# lato1.net
KiCad netlist of a schematic drawn in EAGLE
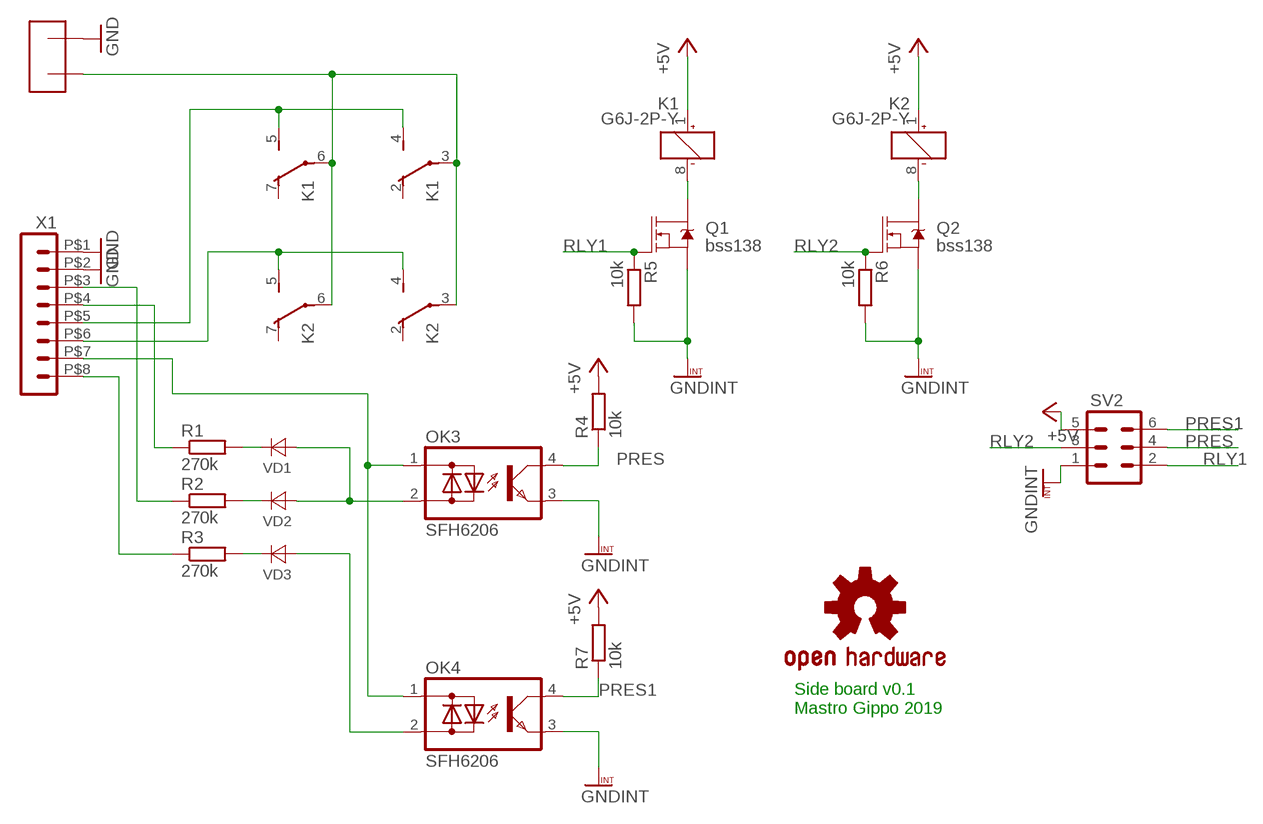
[diagram p0: schematic, sheet 1]

(export (version "E")
  (design (tool "Eeschema 10.0.6"))
  (components
    (comp (ref "K1")
      (value "G6J-2P-Y")
      (footprint "eagle-import:G6J-2P-Y")
      (fields (field (name "MF") "OMRON COMPONENTS USA") (field (name "MPN") "G6J-2P-Y-DC12"))
      (libsource (lib "eagle-import") (part "G6J-2?-YP"))
    )
    (comp (ref "K2")
      (value "G6J-2P-Y")
      (footprint "eagle-import:G6J-2P-Y")
      (fields (field (name "MF") "OMRON COMPONENTS USA") (field (name "MPN") "G6J-2P-Y-DC12"))
      (libsource (lib "eagle-import") (part "G6J-2?-YP"))
    )
    (comp (ref "OK3")
      (value "SFH6206")
      (footprint "eagle-import:DIL4-SMD")
      (fields (field (name "MF") "VISHAY/TELEFUNKEN") (field (name "MPN") "SFH6206-3"))
      (libsource (lib "eagle-import") (part "SFH6206"))
    )
    (comp (ref "OK4")
      (value "SFH6206")
      (footprint "eagle-import:DIL4-SMD")
      (fields (field (name "MF") "VISHAY/TELEFUNKEN") (field (name "MPN") "SFH6206-3"))
      (libsource (lib "eagle-import") (part "SFH6206"))
    )
    (comp (ref "Q1")
      (value "bss138")
      (footprint "eagle-import:SOT23-3")
      (libsource (lib "eagle-import") (part "MOSFET-NCH-BSS138"))
    )
    (comp (ref "Q2")
      (value "bss138")
      (footprint "eagle-import:SOT23-3")
      (libsource (lib "eagle-import") (part "MOSFET-NCH-BSS138"))
    )
    (comp (ref "R1")
      (value "270k")
      (footprint "eagle-import:R1210")
      (libsource (lib "eagle-import") (part "R-EU_R1210"))
    )
    (comp (ref "R2")
      (value "270k")
      (footprint "eagle-import:R1210")
      (libsource (lib "eagle-import") (part "R-EU_R1210"))
    )
    (comp (ref "R3")
      (value "270k")
      (footprint "eagle-import:R1210")
      (libsource (lib "eagle-import") (part "R-EU_R1210"))
    )
    (comp (ref "R4")
      (value "10k")
      (footprint "eagle-import:R0805")
      (libsource (lib "eagle-import") (part "R-EU_R0805"))
    )
    (comp (ref "R5")
      (value "10k")
      (footprint "eagle-import:R0805")
      (libsource (lib "eagle-import") (part "R-EU_R0805"))
    )
    (comp (ref "R6")
      (value "10k")
      (footprint "eagle-import:R0805")
      (libsource (lib "eagle-import") (part "R-EU_R0805"))
    )
    (comp (ref "R7")
      (value "10k")
      (footprint "eagle-import:R0805")
      (libsource (lib "eagle-import") (part "R-EU_R0805"))
    )
    (comp (ref "SV2")
      (value "MA03-2")
      (footprint "eagle-import:MA03-2")
      (libsource (lib "eagle-import") (part "MA03-2"))
    )
    (comp (ref "U$1")
      (value "ISOLATED_2P")
      (footprint "eagle-import:STRIP_NOMIDDLE")
      (libsource (lib "eagle-import") (part "ISOLATED_2P"))
    )
    (comp (ref "U$2")
      (value "OSHW-LOGOS")
      (footprint "eagle-import:OSHW-LOGO-S")
      (libsource (lib "eagle-import") (part "OSHW-LOGOS"))
    )
    (comp (ref "VD1")
      (value "DIODE-STANDARD-SOD323")
      (footprint "eagle-import:SOD323")
      (libsource (lib "eagle-import") (part "DIODE-STANDARD-SOD323"))
    )
    (comp (ref "VD2")
      (value "DIODE-STANDARD-SOD323")
      (footprint "eagle-import:SOD323")
      (libsource (lib "eagle-import") (part "DIODE-STANDARD-SOD323"))
    )
    (comp (ref "VD3")
      (value "DIODE-STANDARD-SOD323")
      (footprint "eagle-import:SOD323")
      (libsource (lib "eagle-import") (part "DIODE-STANDARD-SOD323"))
    )
    (comp (ref "X1")
      (value "HEADER_POS8_43045-0812")
      (footprint "eagle-import:43045-0812")
      (libsource (lib "eagle-import") (part "HEADER_POS8_?43045-0812"))
    )
  )
  (nets
    (net (code "1") (name "+5V") (class "Default")
      (node (ref "K1") (pin "1") (pinfunction "+_1") (pintype "passive"))
      (node (ref "K2") (pin "1") (pinfunction "+_1") (pintype "passive"))
      (node (ref "R4") (pin "2") (pinfunction "2_2") (pintype "passive"))
      (node (ref "R7") (pin "2") (pinfunction "2_2") (pintype "passive"))
      (node (ref "SV2") (pin "5") (pinfunction "5_5") (pintype "passive"))
    )
    (net (code "2") (name "/PRES") (class "Default")
      (node (ref "OK3") (pin "4") (pinfunction "C_4") (pintype "passive"))
      (node (ref "R4") (pin "1") (pinfunction "1_1") (pintype "passive"))
      (node (ref "SV2") (pin "4") (pinfunction "4_4") (pintype "passive"))
    )
    (net (code "3") (name "/PRES1") (class "Default")
      (node (ref "OK4") (pin "4") (pinfunction "C_4") (pintype "passive"))
      (node (ref "R7") (pin "1") (pinfunction "1_1") (pintype "passive"))
      (node (ref "SV2") (pin "6") (pinfunction "6_6") (pintype "passive"))
    )
    (net (code "4") (name "/RLY1") (class "Default")
      (node (ref "Q1") (pin "1") (pinfunction "G_1") (pintype "bidirectional"))
      (node (ref "R5") (pin "1") (pinfunction "1_1") (pintype "passive"))
      (node (ref "SV2") (pin "2") (pinfunction "2_2") (pintype "passive"))
    )
    (net (code "5") (name "/RLY2") (class "Default")
      (node (ref "Q2") (pin "1") (pinfunction "G_1") (pintype "bidirectional"))
      (node (ref "R6") (pin "1") (pinfunction "1_1") (pintype "passive"))
      (node (ref "SV2") (pin "3") (pinfunction "3_3") (pintype "passive"))
    )
    (net (code "6") (name "GND") (class "Default")
      (node (ref "U$1") (pin "P$1") (pinfunction "P$1_P$1") (pintype "bidirectional"))
      (node (ref "X1") (pin "P$1") (pinfunction "1_P$1") (pintype "passive"))
      (node (ref "X1") (pin "P$2") (pinfunction "2_P$2") (pintype "passive"))
    )
    (net (code "7") (name "GNDINT") (class "Default")
      (node (ref "OK3") (pin "3") (pinfunction "E_3") (pintype "passive"))
      (node (ref "OK4") (pin "3") (pinfunction "E_3") (pintype "passive"))
      (node (ref "Q1") (pin "2") (pinfunction "S_2") (pintype "bidirectional"))
      (node (ref "Q2") (pin "2") (pinfunction "S_2") (pintype "bidirectional"))
      (node (ref "R5") (pin "2") (pinfunction "2_2") (pintype "passive"))
      (node (ref "R6") (pin "2") (pinfunction "2_2") (pintype "passive"))
      (node (ref "SV2") (pin "1") (pinfunction "1_1") (pintype "passive"))
    )
    (net (code "8") (name "Net-(K1A--)") (class "Default")
      (node (ref "K1") (pin "8") (pinfunction "-_8") (pintype "passive"))
      (node (ref "Q1") (pin "3") (pinfunction "D_3") (pintype "bidirectional"))
    )
    (net (code "9") (name "Net-(K1B-P)") (class "Default")
      (node (ref "K1") (pin "3") (pinfunction "P_3") (pintype "passive"))
      (node (ref "K1") (pin "6") (pinfunction "P_6") (pintype "passive"))
      (node (ref "K2") (pin "3") (pinfunction "P_3") (pintype "passive"))
      (node (ref "K2") (pin "6") (pinfunction "P_6") (pintype "passive"))
      (node (ref "U$1") (pin "P$2") (pinfunction "P$2_P$2") (pintype "bidirectional"))
    )
    (net (code "10") (name "Net-(K1B-S)") (class "Default")
      (node (ref "K1") (pin "4") (pinfunction "S_4") (pintype "passive"))
      (node (ref "K1") (pin "5") (pinfunction "S_5") (pintype "passive"))
      (node (ref "X1") (pin "P$5") (pinfunction "5_P$5") (pintype "passive"))
    )
    (net (code "11") (name "Net-(K2A--)") (class "Default")
      (node (ref "K2") (pin "8") (pinfunction "-_8") (pintype "passive"))
      (node (ref "Q2") (pin "3") (pinfunction "D_3") (pintype "bidirectional"))
    )
    (net (code "12") (name "Net-(K2B-S)") (class "Default")
      (node (ref "K2") (pin "4") (pinfunction "S_4") (pintype "passive"))
      (node (ref "K2") (pin "5") (pinfunction "S_5") (pintype "passive"))
      (node (ref "X1") (pin "P$6") (pinfunction "6_P$6") (pintype "passive"))
    )
    (net (code "13") (name "Net-(OK3-AC1)") (class "Default")
      (node (ref "OK3") (pin "1") (pinfunction "AC1_1") (pintype "passive"))
      (node (ref "OK4") (pin "1") (pinfunction "AC1_1") (pintype "passive"))
      (node (ref "X1") (pin "P$7") (pinfunction "7_P$7") (pintype "passive"))
    )
    (net (code "14") (name "Net-(OK3-AC2)") (class "Default")
      (node (ref "OK3") (pin "2") (pinfunction "AC2_2") (pintype "passive"))
      (node (ref "VD1") (pin "A") (pinfunction "A_A") (pintype "passive"))
      (node (ref "VD2") (pin "A") (pinfunction "A_A") (pintype "passive"))
    )
    (net (code "15") (name "Net-(OK4-AC2)") (class "Default")
      (node (ref "OK4") (pin "2") (pinfunction "AC2_2") (pintype "passive"))
      (node (ref "VD3") (pin "A") (pinfunction "A_A") (pintype "passive"))
    )
    (net (code "16") (name "Net-(R1-Pad2)") (class "Default")
      (node (ref "R1") (pin "2") (pinfunction "2_2") (pintype "passive"))
      (node (ref "VD1") (pin "C") (pinfunction "C_C") (pintype "passive"))
    )
    (net (code "17") (name "Net-(R2-Pad2)") (class "Default")
      (node (ref "R2") (pin "2") (pinfunction "2_2") (pintype "passive"))
      (node (ref "VD2") (pin "C") (pinfunction "C_C") (pintype "passive"))
    )
    (net (code "18") (name "Net-(R3-Pad2)") (class "Default")
      (node (ref "R3") (pin "2") (pinfunction "2_2") (pintype "passive"))
      (node (ref "VD3") (pin "C") (pinfunction "C_C") (pintype "passive"))
    )
    (net (code "19") (name "Net-(X1-3)") (class "Default")
      (node (ref "R2") (pin "1") (pinfunction "1_1") (pintype "passive"))
      (node (ref "X1") (pin "P$3") (pinfunction "3_P$3") (pintype "passive"))
    )
    (net (code "20") (name "Net-(X1-4)") (class "Default")
      (node (ref "R1") (pin "1") (pinfunction "1_1") (pintype "passive"))
      (node (ref "X1") (pin "P$4") (pinfunction "4_P$4") (pintype "passive"))
    )
    (net (code "21") (name "Net-(X1-8)") (class "Default")
      (node (ref "R3") (pin "1") (pinfunction "1_1") (pintype "passive"))
      (node (ref "X1") (pin "P$8") (pinfunction "8_P$8") (pintype "passive"))
    )
    (net (code "22") (name "unconnected-(K1B-O-Pad2)") (class "Default")
      (node (ref "K1") (pin "2") (pinfunction "O_2") (pintype "passive"))
    )
    (net (code "23") (name "unconnected-(K1C-O-Pad7)") (class "Default")
      (node (ref "K1") (pin "7") (pinfunction "O_7") (pintype "passive"))
    )
    (net (code "24") (name "unconnected-(K2B-O-Pad2)") (class "Default")
      (node (ref "K2") (pin "2") (pinfunction "O_2") (pintype "passive"))
    )
    (net (code "25") (name "unconnected-(K2C-O-Pad7)") (class "Default")
      (node (ref "K2") (pin "7") (pinfunction "O_7") (pintype "passive"))
    )
  )
)
